# Silent_Stepper_Driver.net
KiCad netlist of a schematic drawn in EAGLE
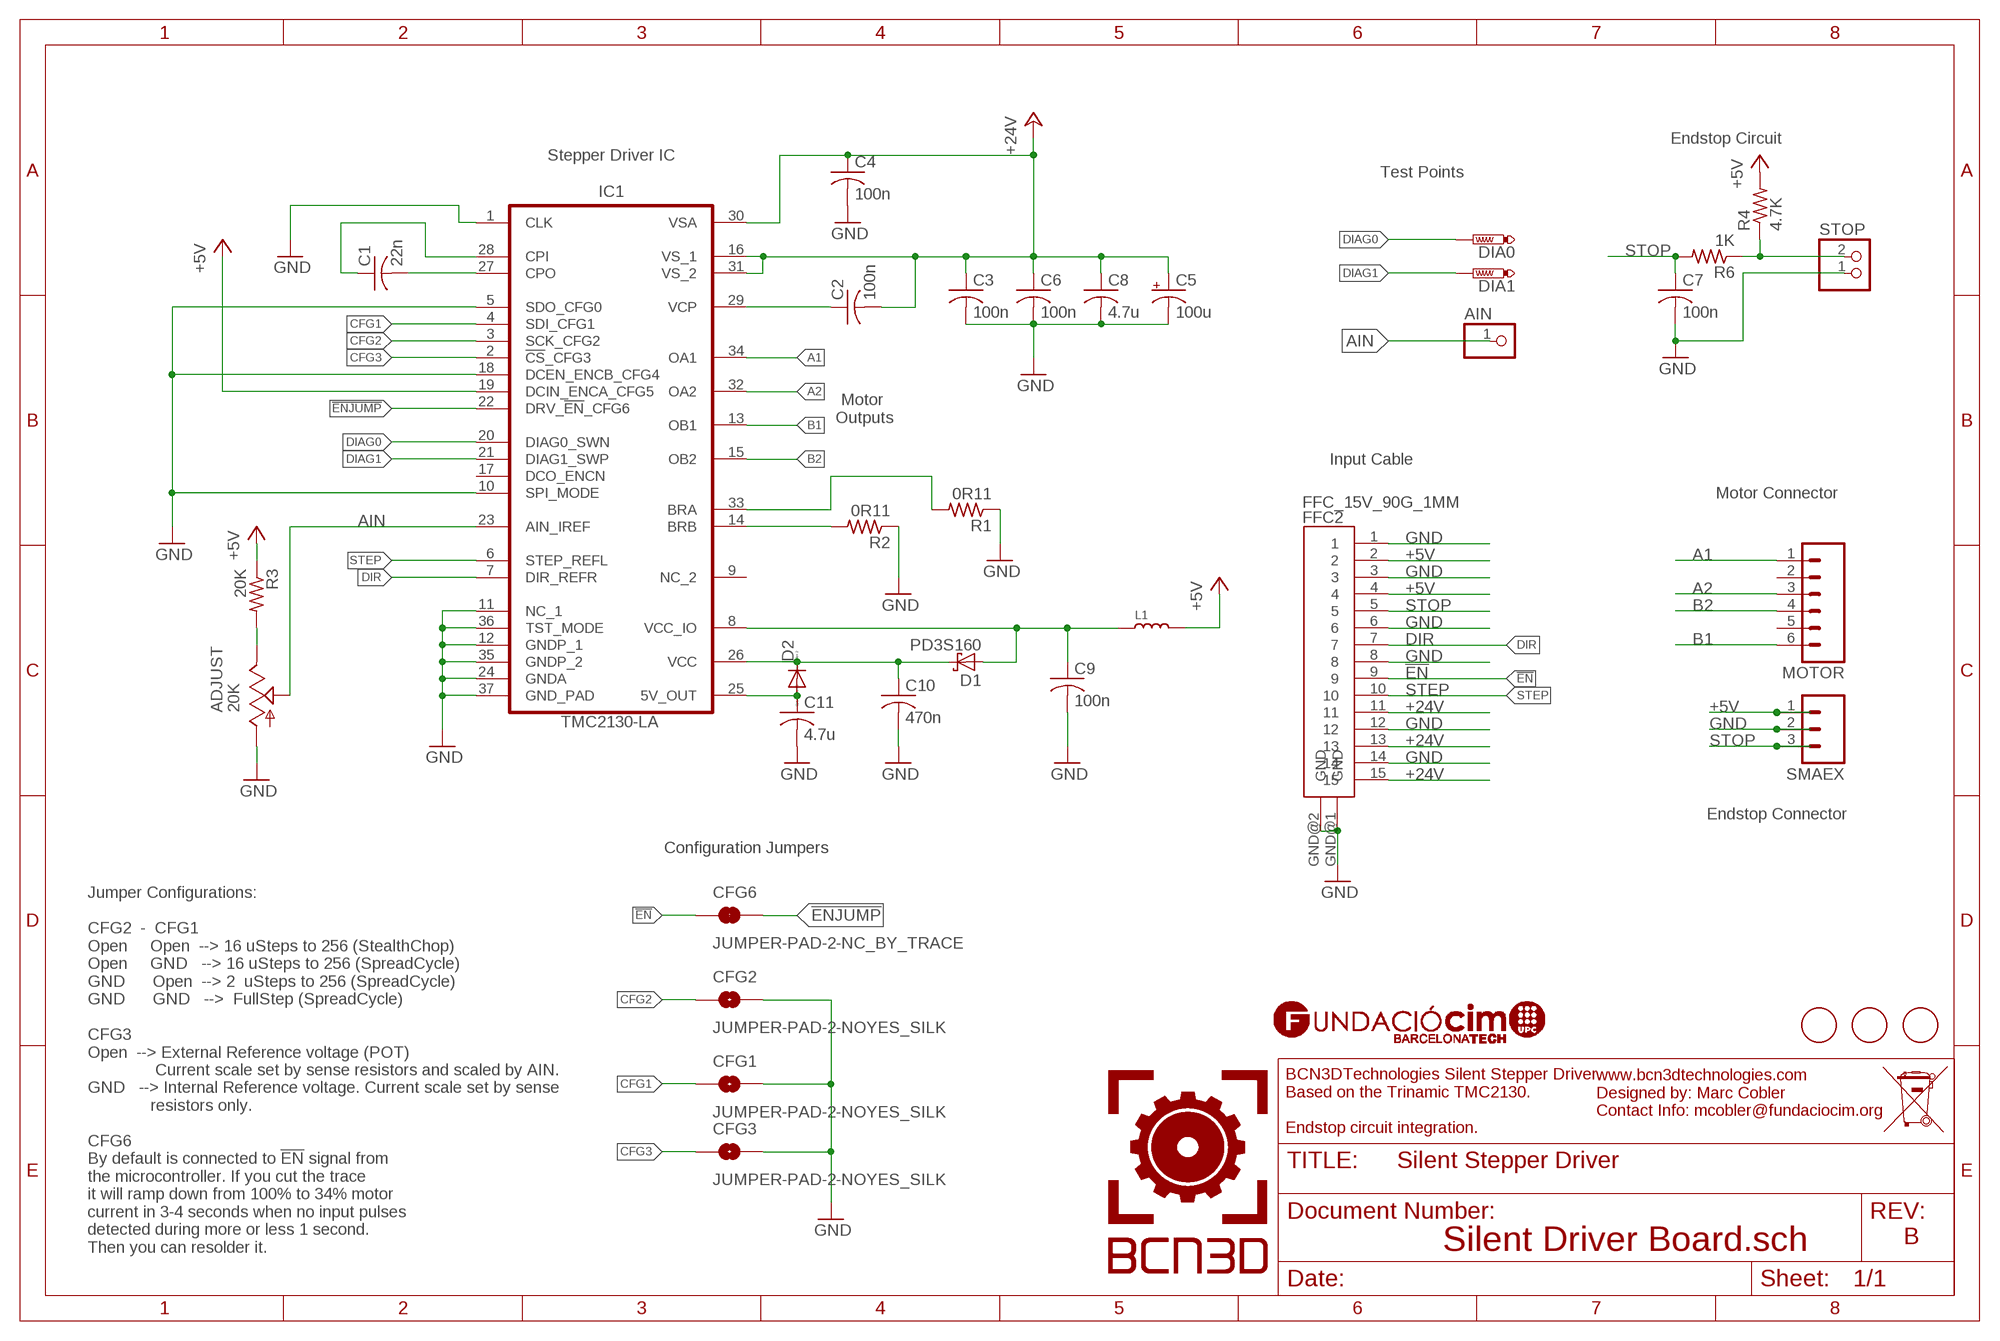
[diagram p0: schematic, sheet 1]

(export (version "E")
  (design (tool "Eeschema 10.0.6"))
  (components
    (comp (ref "ADJUST")
      (value "20K")
      (footprint "eagle-import:3223G")
      (fields (field (name "MF") "BOURNS") (field (name "MPN") "3314G-2-203E"))
      (libsource (lib "eagle-import") (part "TRIM_US-3223G"))
    )
    (comp (ref "AIN")
      (value "PINHD-1X1")
      (footprint "eagle-import:1X01")
      (libsource (lib "eagle-import") (part "PINHD-1X1"))
    )
    (comp (ref "C1")
      (value "22n")
      (footprint "eagle-import:C0603K")
      (fields (field (name "MF") "MURATA") (field (name "MPN") "GCM188R72A223KA37D"))
      (libsource (lib "eagle-import") (part "C-USC0603K"))
    )
    (comp (ref "C2")
      (value "100n")
      (footprint "eagle-import:C0603K")
      (fields (field (name "MF") "AVX") (field (name "MPN") "06035C104KAT2A"))
      (libsource (lib "eagle-import") (part "C-USC0603K"))
    )
    (comp (ref "C3")
      (value "100n")
      (footprint "eagle-import:C0603K")
      (fields (field (name "MF") "AVX") (field (name "MPN") "06035C104KAT2A"))
      (libsource (lib "eagle-import") (part "C-USC0603K"))
    )
    (comp (ref "C4")
      (value "100n")
      (footprint "eagle-import:C0603K")
      (fields (field (name "MF") "AVX") (field (name "MPN") "06035C104KAT2A"))
      (libsource (lib "eagle-import") (part "C-USC0603K"))
    )
    (comp (ref "C5")
      (value "100u")
      (footprint "eagle-import:UD-6,3X7,7_NICHICON")
      (fields (field (name "MF") "PANASONIC ELECTRONIC COMPONENTS") (field (name "MPN") "EEE1HA101UAP"))
      (libsource (lib "eagle-import") (part "CPOL-USUD-6,3X7,7"))
    )
    (comp (ref "C6")
      (value "100n")
      (footprint "eagle-import:C0603K")
      (fields (field (name "MF") "AVX") (field (name "MPN") "06035C104KAT2A"))
      (libsource (lib "eagle-import") (part "C-USC0603K"))
    )
    (comp (ref "C7")
      (value "100n")
      (footprint "eagle-import:C0603K")
      (fields (field (name "MF") "AVX") (field (name "MPN") "06035C104KAT2A"))
      (libsource (lib "eagle-import") (part "C-USC0603K"))
    )
    (comp (ref "C8")
      (value "4.7u")
      (footprint "eagle-import:C1210")
      (fields (field (name "MF") "KEMET") (field (name "MPN") "C1210X475K5RACTU"))
      (libsource (lib "eagle-import") (part "C-USC1210"))
    )
    (comp (ref "C9")
      (value "100n")
      (footprint "eagle-import:C0603K")
      (fields (field (name "MF") "AVX") (field (name "MPN") "06035C104KAT2A"))
      (libsource (lib "eagle-import") (part "C-USC0603K"))
    )
    (comp (ref "C10")
      (value "470n")
      (footprint "eagle-import:C0603K")
      (fields (field (name "MF") "MURATA") (field (name "MPN") "GRM188R71C474KA88D"))
      (libsource (lib "eagle-import") (part "C-USC0603K"))
    )
    (comp (ref "C11")
      (value "4.7u")
      (footprint "eagle-import:C0805")
      (fields (field (name "MF") "AVX") (field (name "MPN") "0805YC475KAT2A"))
      (libsource (lib "eagle-import") (part "C-USC0805"))
    )
    (comp (ref "CFG1")
      (value "JUMPER-PAD-2-NOYES_SILK")
      (footprint "eagle-import:PAD-JUMPER-2-NO_YES_SILK")
      (libsource (lib "eagle-import") (part "JUMPER-PAD-2-NOYES_SILK"))
    )
    (comp (ref "CFG2")
      (value "JUMPER-PAD-2-NOYES_SILK")
      (footprint "eagle-import:PAD-JUMPER-2-NO_YES_SILK")
      (libsource (lib "eagle-import") (part "JUMPER-PAD-2-NOYES_SILK"))
    )
    (comp (ref "CFG3")
      (value "JUMPER-PAD-2-NOYES_SILK")
      (footprint "eagle-import:PAD-JUMPER-2-NO_YES_SILK")
      (libsource (lib "eagle-import") (part "JUMPER-PAD-2-NOYES_SILK"))
    )
    (comp (ref "CFG6")
      (value "JUMPER-PAD-2-NC_BY_TRACE")
      (footprint "eagle-import:PAD-JUMPER-2-NC_BY_TRACE_YES_SILK")
      (libsource (lib "eagle-import") (part "JUMPER-PAD-2-NC_BY_TRACE"))
    )
    (comp (ref "D1")
      (value "PD3S160")
      (footprint "eagle-import:POWERDI323")
      (fields (field (name "MF") "DIODES INC.") (field (name "MPN") "PD3S160-7"))
      (libsource (lib "eagle-import") (part "PD3S160"))
    )
    (comp (ref "D2")
      (value "DIODE-MINIMELF")
      (footprint "eagle-import:MINIMELF")
      (fields (field (name "MF") "NXP") (field (name "MPN") "PMLL4448"))
      (libsource (lib "eagle-import") (part "DIODE-MINIMELF"))
    )
    (comp (ref "DIA0")
      (value "PTR1TP12R")
      (footprint "eagle-import:TP12R")
      (libsource (lib "eagle-import") (part "PTR1TP12R"))
    )
    (comp (ref "DIA1")
      (value "PTR1TP12R")
      (footprint "eagle-import:TP12R")
      (libsource (lib "eagle-import") (part "PTR1TP12R"))
    )
    (comp (ref "FFC2")
      (value "FFC_15V_90G_1MM")
      (footprint "eagle-import:TE_FFC_CON1MM")
      (libsource (lib "eagle-import") (part "FFC_15V_90G_1MM"))
    )
    (comp (ref "IC1")
      (value "TMC2130-LA")
      (footprint "eagle-import:TMC_QFN36_0.5_5.0X6.0")
      (fields (field (name "MANUFACTURER") " TRINAMIC "))
      (libsource (lib "eagle-import") (part "TMC2130-LA"))
    )
    (comp (ref "L1")
      (value "INDUCTOR/FERRITE-BEAD'0603'")
      (footprint "eagle-import:L0603")
      (libsource (lib "eagle-import") (part "INDUCTOR/FERRITE-BEAD'0603'"))
    )
    (comp (ref "MOTOR")
      (value "M06")
      (footprint "eagle-import:JST-6-PTH")
      (fields
        (field (name "MF") "JST (JAPAN SOLDERLESS TERMINALS)")
        (field (name "MPN") "S6B-PH-K-S (LF)(SN)")
      )
      (libsource (lib "eagle-import") (part "M06"))
    )
    (comp (ref "R1")
      (value "0R11")
      (footprint "eagle-import:R0805")
      (fields (field (name "MF") "PANASONIC ELECTRONIC COMPONENTS") (field (name "MPN") "ERJ6BSFR11V"))
      (libsource (lib "eagle-import") (part "R-US_R0805"))
    )
    (comp (ref "R2")
      (value "0R11")
      (footprint "eagle-import:R0805")
      (fields (field (name "MF") "PANASONIC ELECTRONIC COMPONENTS") (field (name "MPN") "ERJ6BSFR11V"))
      (libsource (lib "eagle-import") (part "R-US_R0805"))
    )
    (comp (ref "R3")
      (value "20K")
      (footprint "eagle-import:R0603")
      (fields (field (name "MF") "MULTICOMP") (field (name "MPN") "MC0201L6F2002SE."))
      (libsource (lib "eagle-import") (part "R-US_R0603"))
    )
    (comp (ref "R4")
      (value "4.7K")
      (footprint "eagle-import:R0603")
      (fields (field (name "MF") "PANASONIC ELECTRONIC COMPONENTS") (field (name "MPN") "ERJP06F4701V"))
      (libsource (lib "eagle-import") (part "R-US_R0603"))
    )
    (comp (ref "R6")
      (value "1K")
      (footprint "eagle-import:R0603")
      (fields (field (name "MF") "BOURNS") (field (name "MPN") "CR0805-JW-102ELF"))
      (libsource (lib "eagle-import") (part "R-US_R0603"))
    )
    (comp (ref "SMAEX")
      (value "M03PTH")
      (footprint "eagle-import:1X03")
      (libsource (lib "eagle-import") (part "M03PTH"))
    )
    (comp (ref "STOP")
      (value "JST_2PIN-THM-RA")
      (footprint "eagle-import:JST-PH-2-THM-RA")
      (fields
        (field (name "MF") "JST (JAPAN SOLDERLESS TERMINALS)")
        (field (name "MPN") "S2B-PH-K-S (LF)(SN)")
      )
      (libsource (lib "eagle-import") (part "JST_2PIN-THM-RA"))
    )
    (comp (ref "U$2")
      (value "FIDUCIAL")
      (footprint "eagle-import:FIDUCIAL_1MM")
      (libsource (lib "eagle-import") (part "FIDUCIAL"))
    )
    (comp (ref "U$3")
      (value "FIDUCIAL")
      (footprint "eagle-import:FIDUCIAL_1MM")
      (libsource (lib "eagle-import") (part "FIDUCIAL"))
    )
    (comp (ref "U$4")
      (value "FIDUCIAL")
      (footprint "eagle-import:FIDUCIAL_1MM")
      (libsource (lib "eagle-import") (part "FIDUCIAL"))
    )
  )
  (nets
    (net (code "1") (name "+5V") (class "Default")
      (node (ref "FFC2") (pin "2") (pinfunction "2_2") (pintype "bidirectional"))
      (node (ref "FFC2") (pin "4") (pinfunction "4_4") (pintype "bidirectional"))
      (node (ref "IC1") (pin "19") (pinfunction "DCIN_ENCA_CFG5_19") (pintype "input"))
      (node (ref "L1") (pin "2") (pinfunction "2_2") (pintype "passive"))
      (node (ref "R3") (pin "1") (pinfunction "1_1") (pintype "passive"))
      (node (ref "R4") (pin "2") (pinfunction "2_2") (pintype "passive"))
      (node (ref "SMAEX") (pin "1") (pinfunction "1_1") (pintype "passive"))
    )
    (net (code "2") (name "+24V") (class "Default")
      (node (ref "C2") (pin "2") (pinfunction "2_2") (pintype "passive"))
      (node (ref "C3") (pin "1") (pinfunction "1_1") (pintype "passive"))
      (node (ref "C4") (pin "1") (pinfunction "1_1") (pintype "passive"))
      (node (ref "C5") (pin "+") (pinfunction "+_+") (pintype "passive"))
      (node (ref "C6") (pin "1") (pinfunction "1_1") (pintype "passive"))
      (node (ref "C8") (pin "1") (pinfunction "1_1") (pintype "passive"))
      (node (ref "FFC2") (pin "11") (pinfunction "11_11") (pintype "bidirectional"))
      (node (ref "FFC2") (pin "13") (pinfunction "13_13") (pintype "bidirectional"))
      (node (ref "FFC2") (pin "15") (pinfunction "15_15") (pintype "bidirectional"))
      (node (ref "IC1") (pin "16") (pinfunction "VS_1_16") (pintype "power_in"))
      (node (ref "IC1") (pin "30") (pinfunction "VSA_30") (pintype "power_in"))
      (node (ref "IC1") (pin "31") (pinfunction "VS_2_31") (pintype "power_in"))
    )
    (net (code "3") (name "/STOP") (class "Default")
      (node (ref "C7") (pin "1") (pinfunction "1_1") (pintype "passive"))
      (node (ref "FFC2") (pin "5") (pinfunction "5_5") (pintype "bidirectional"))
      (node (ref "R6") (pin "2") (pinfunction "2_2") (pintype "passive"))
      (node (ref "SMAEX") (pin "3") (pinfunction "3_3") (pintype "passive"))
    )
    (net (code "4") (name "/~{ENJUMP}") (class "Default")
      (node (ref "CFG6") (pin "2") (pinfunction "2_2") (pintype "passive"))
      (node (ref "IC1") (pin "22") (pinfunction "DRV_~{EN}_CFG6_22") (pintype "input"))
    )
    (net (code "5") (name "/~{EN}") (class "Default")
      (node (ref "CFG6") (pin "1") (pinfunction "1_1") (pintype "passive"))
      (node (ref "FFC2") (pin "9") (pinfunction "9_9") (pintype "bidirectional"))
    )
    (net (code "6") (name "A1") (class "Default")
      (node (ref "IC1") (pin "34") (pinfunction "OA1_34") (pintype "output"))
      (node (ref "MOTOR") (pin "1") (pinfunction "1_1") (pintype "passive"))
    )
    (net (code "7") (name "A2") (class "Default")
      (node (ref "IC1") (pin "32") (pinfunction "OA2_32") (pintype "output"))
      (node (ref "MOTOR") (pin "3") (pinfunction "3_3") (pintype "passive"))
    )
    (net (code "8") (name "AIN") (class "Default")
      (node (ref "ADJUST") (pin "2") (pinfunction "S_2") (pintype "passive"))
      (node (ref "AIN") (pin "1") (pinfunction "1_1") (pintype "passive"))
      (node (ref "IC1") (pin "23") (pinfunction "AIN_IREF_23") (pintype "input"))
    )
    (net (code "9") (name "B1") (class "Default")
      (node (ref "IC1") (pin "13") (pinfunction "OB1_13") (pintype "output"))
      (node (ref "MOTOR") (pin "6") (pinfunction "6_6") (pintype "passive"))
    )
    (net (code "10") (name "B2") (class "Default")
      (node (ref "IC1") (pin "15") (pinfunction "OB2_15") (pintype "output"))
      (node (ref "MOTOR") (pin "4") (pinfunction "4_4") (pintype "passive"))
    )
    (net (code "11") (name "CFG1") (class "Default")
      (node (ref "CFG1") (pin "1") (pinfunction "1_1") (pintype "passive"))
      (node (ref "IC1") (pin "4") (pinfunction "SDI_CFG1_4") (pintype "input"))
    )
    (net (code "12") (name "CFG2") (class "Default")
      (node (ref "CFG2") (pin "1") (pinfunction "1_1") (pintype "passive"))
      (node (ref "IC1") (pin "3") (pinfunction "SCK_CFG2_3") (pintype "input"))
    )
    (net (code "13") (name "CFG3") (class "Default")
      (node (ref "CFG3") (pin "1") (pinfunction "1_1") (pintype "passive"))
      (node (ref "IC1") (pin "2") (pinfunction "~{CS}_CFG3_2") (pintype "input"))
    )
    (net (code "14") (name "DIAG0") (class "Default")
      (node (ref "DIA0") (pin "TP") (pinfunction "TP_TP") (pintype "input"))
      (node (ref "IC1") (pin "20") (pinfunction "DIAG0_SWN_20") (pintype "bidirectional"))
    )
    (net (code "15") (name "DIAG1") (class "Default")
      (node (ref "DIA1") (pin "TP") (pinfunction "TP_TP") (pintype "input"))
      (node (ref "IC1") (pin "21") (pinfunction "DIAG1_SWP_21") (pintype "bidirectional"))
    )
    (net (code "16") (name "DIR") (class "Default")
      (node (ref "FFC2") (pin "7") (pinfunction "7_7") (pintype "bidirectional"))
      (node (ref "IC1") (pin "7") (pinfunction "DIR_REFR_7") (pintype "input"))
    )
    (net (code "17") (name "GND") (class "Default")
      (node (ref "ADJUST") (pin "1") (pinfunction "A_1") (pintype "passive"))
      (node (ref "C10") (pin "2") (pinfunction "2_2") (pintype "passive"))
      (node (ref "C11") (pin "2") (pinfunction "2_2") (pintype "passive"))
      (node (ref "C3") (pin "2") (pinfunction "2_2") (pintype "passive"))
      (node (ref "C4") (pin "2") (pinfunction "2_2") (pintype "passive"))
      (node (ref "C5") (pin "-") (pinfunction "-_-") (pintype "passive"))
      (node (ref "C6") (pin "2") (pinfunction "2_2") (pintype "passive"))
      (node (ref "C7") (pin "2") (pinfunction "2_2") (pintype "passive"))
      (node (ref "C8") (pin "2") (pinfunction "2_2") (pintype "passive"))
      (node (ref "C9") (pin "2") (pinfunction "2_2") (pintype "passive"))
      (node (ref "CFG1") (pin "2") (pinfunction "2_2") (pintype "passive"))
      (node (ref "CFG2") (pin "2") (pinfunction "2_2") (pintype "passive"))
      (node (ref "CFG3") (pin "2") (pinfunction "2_2") (pintype "passive"))
      (node (ref "FFC2") (pin "1") (pinfunction "1_1") (pintype "bidirectional"))
      (node (ref "FFC2") (pin "12") (pinfunction "12_12") (pintype "bidirectional"))
      (node (ref "FFC2") (pin "14") (pinfunction "14_14") (pintype "bidirectional"))
      (node (ref "FFC2") (pin "3") (pinfunction "3_3") (pintype "bidirectional"))
      (node (ref "FFC2") (pin "6") (pinfunction "6_6") (pintype "bidirectional"))
      (node (ref "FFC2") (pin "8") (pinfunction "8_8") (pintype "bidirectional"))
      (node (ref "FFC2") (pin "GND@1") (pinfunction "GND_GND@1") (pintype "bidirectional"))
      (node (ref "FFC2") (pin "GND@2") (pinfunction "GND_GND@2") (pintype "bidirectional"))
      (node (ref "IC1") (pin "1") (pinfunction "CLK_1") (pintype "input"))
      (node (ref "IC1") (pin "10") (pinfunction "SPI_MODE_10") (pintype "input"))
      (node (ref "IC1") (pin "11") (pinfunction "NC_1_11") (pintype "power_in"))
      (node (ref "IC1") (pin "12") (pinfunction "GNDP_1_12") (pintype "power_in"))
      (node (ref "IC1") (pin "18") (pinfunction "DCEN_ENCB_CFG4_18") (pintype "input"))
      (node (ref "IC1") (pin "24") (pinfunction "GNDA_24") (pintype "power_in"))
      (node (ref "IC1") (pin "35") (pinfunction "GNDP_2_35") (pintype "power_in"))
      (node (ref "IC1") (pin "36") (pinfunction "TST_MODE_36") (pintype "input"))
      (node (ref "IC1") (pin "37") (pinfunction "GND_PAD_37") (pintype "power_in"))
      (node (ref "IC1") (pin "5") (pinfunction "SDO_CFG0_5") (pintype "bidirectional"))
      (node (ref "R1") (pin "1") (pinfunction "1_1") (pintype "passive"))
      (node (ref "R2") (pin "1") (pinfunction "1_1") (pintype "passive"))
      (node (ref "SMAEX") (pin "2") (pinfunction "2_2") (pintype "passive"))
      (node (ref "STOP") (pin "1") (pinfunction "2_1") (pintype "passive"))
    )
    (net (code "18") (name "Net-(ADJUST-E)") (class "Default")
      (node (ref "ADJUST") (pin "3") (pinfunction "E_3") (pintype "passive"))
      (node (ref "R3") (pin "2") (pinfunction "2_2") (pintype "passive"))
    )
    (net (code "19") (name "Net-(IC1-5V_OUT)") (class "Default")
      (node (ref "C11") (pin "1") (pinfunction "1_1") (pintype "passive"))
      (node (ref "D2") (pin "A") (pinfunction "A_A") (pintype "passive"))
      (node (ref "IC1") (pin "25") (pinfunction "5V_OUT_25") (pintype "power_in"))
    )
    (net (code "20") (name "Net-(IC1-BRA)") (class "Default")
      (node (ref "IC1") (pin "33") (pinfunction "BRA_33") (pintype "output"))
      (node (ref "R1") (pin "2") (pinfunction "2_2") (pintype "passive"))
    )
    (net (code "21") (name "Net-(IC1-BRB)") (class "Default")
      (node (ref "IC1") (pin "14") (pinfunction "BRB_14") (pintype "output"))
      (node (ref "R2") (pin "2") (pinfunction "2_2") (pintype "passive"))
    )
    (net (code "22") (name "Net-(IC1-CPI)") (class "Default")
      (node (ref "C1") (pin "1") (pinfunction "1_1") (pintype "passive"))
      (node (ref "IC1") (pin "28") (pinfunction "CPI_28") (pintype "input"))
    )
    (net (code "23") (name "Net-(IC1-CPO)") (class "Default")
      (node (ref "C1") (pin "2") (pinfunction "2_2") (pintype "passive"))
      (node (ref "IC1") (pin "27") (pinfunction "CPO_27") (pintype "output"))
    )
    (net (code "24") (name "Net-(IC1-VCC)") (class "Default")
      (node (ref "C10") (pin "1") (pinfunction "1_1") (pintype "passive"))
      (node (ref "D1") (pin "C") (pinfunction "C_C") (pintype "passive"))
      (node (ref "D2") (pin "C") (pinfunction "C_C") (pintype "passive"))
      (node (ref "IC1") (pin "26") (pinfunction "VCC_26") (pintype "power_in"))
    )
    (net (code "25") (name "Net-(IC1-VCC_IO)") (class "Default")
      (node (ref "C9") (pin "1") (pinfunction "1_1") (pintype "passive"))
      (node (ref "D1") (pin "A") (pinfunction "A_A") (pintype "passive"))
      (node (ref "IC1") (pin "8") (pinfunction "VCC_IO_8") (pintype "power_in"))
      (node (ref "L1") (pin "1") (pinfunction "1_1") (pintype "passive"))
    )
    (net (code "26") (name "Net-(IC1-VCP)") (class "Default")
      (node (ref "C2") (pin "1") (pinfunction "1_1") (pintype "passive"))
      (node (ref "IC1") (pin "29") (pinfunction "VCP_29") (pintype "power_in"))
    )
    (net (code "27") (name "Net-(STOP-1)") (class "Default")
      (node (ref "R4") (pin "1") (pinfunction "1_1") (pintype "passive"))
      (node (ref "R6") (pin "1") (pinfunction "1_1") (pintype "passive"))
      (node (ref "STOP") (pin "2") (pinfunction "1_2") (pintype "passive"))
    )
    (net (code "28") (name "STEP") (class "Default")
      (node (ref "FFC2") (pin "10") (pinfunction "10_10") (pintype "bidirectional"))
      (node (ref "IC1") (pin "6") (pinfunction "STEP_REFL_6") (pintype "input"))
    )
    (net (code "29") (name "unconnected-(IC1-DCO_ENCN-Pad17)") (class "Default")
      (node (ref "IC1") (pin "17") (pinfunction "DCO_ENCN_17") (pintype "bidirectional"))
    )
    (net (code "30") (name "unconnected-(IC1-NC_2-Pad9)") (class "Default")
      (node (ref "IC1") (pin "9") (pinfunction "NC_2_9") (pintype "passive"))
    )
    (net (code "31") (name "unconnected-(MOTOR-Pad2)") (class "Default")
      (node (ref "MOTOR") (pin "2") (pinfunction "2_2") (pintype "passive"))
    )
    (net (code "32") (name "unconnected-(MOTOR-Pad5)") (class "Default")
      (node (ref "MOTOR") (pin "5") (pinfunction "5_5") (pintype "passive"))
    )
  )
)
